# design.net
KiCad netlist of a schematic drawn in EasyEDA Pro
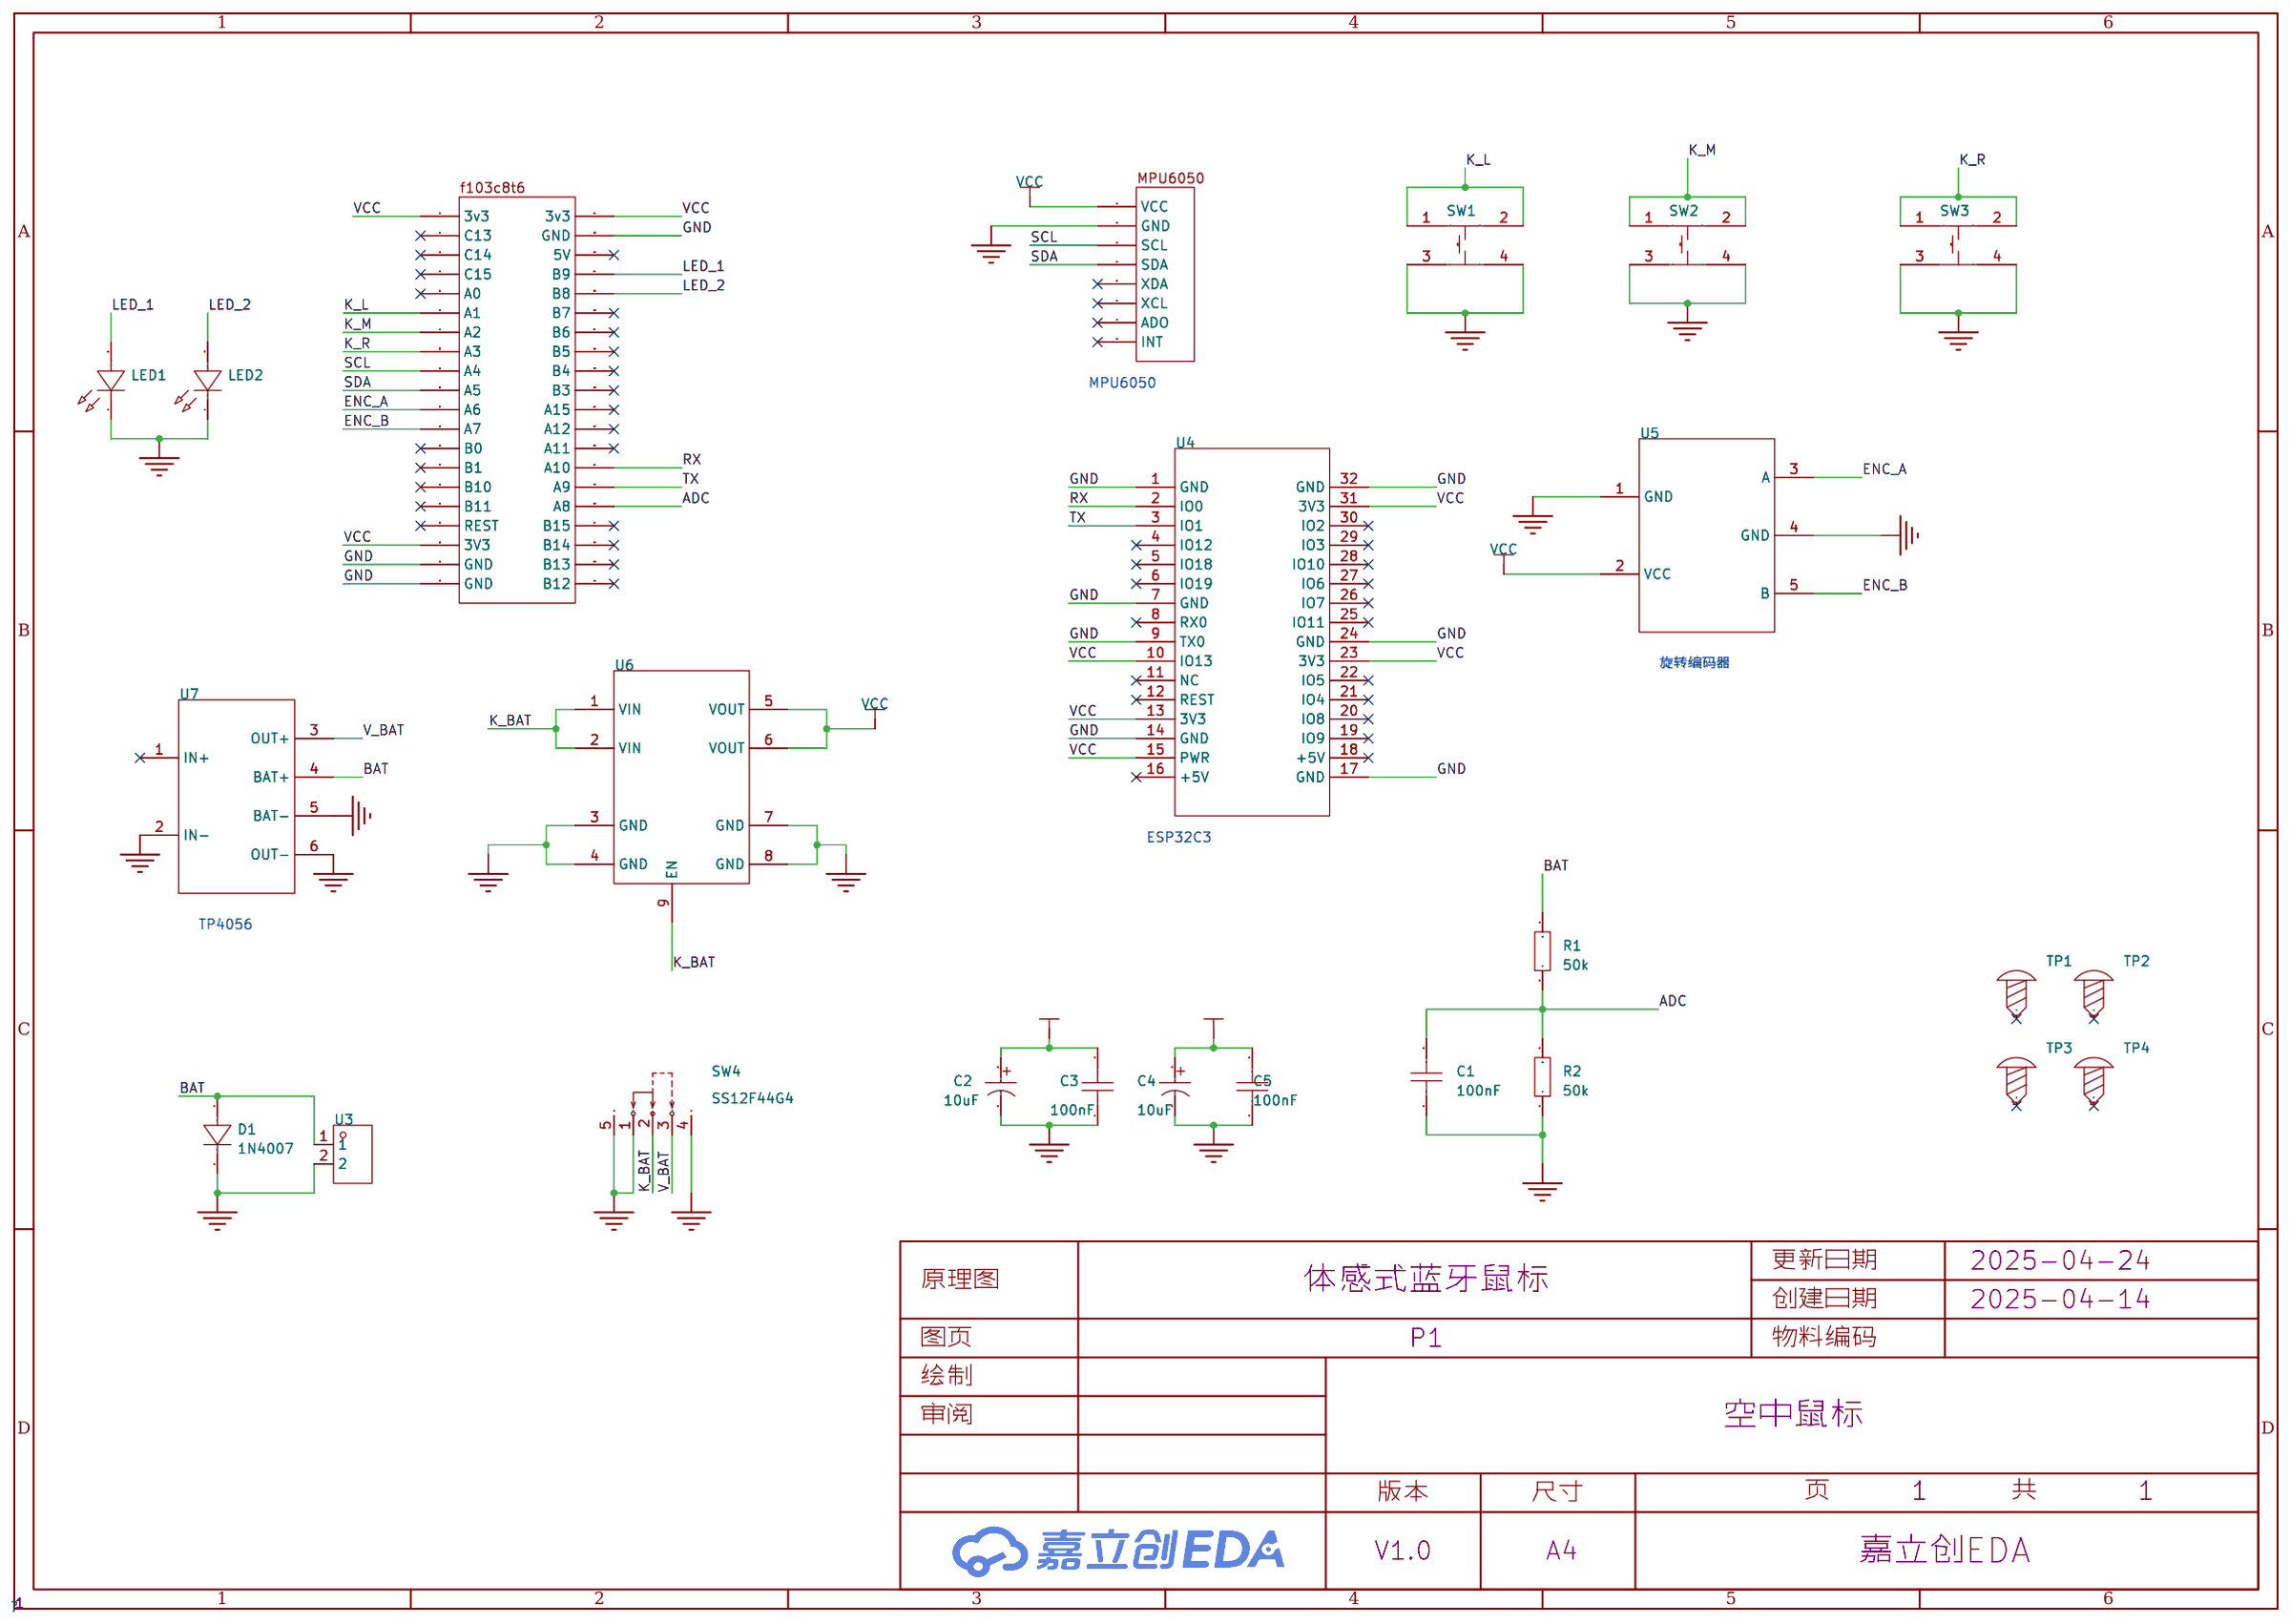
[diagram p0: schematic sheet]

(export (version "E")
  (design (tool "Eeschema 10.0.6"))
  (components
    (comp (ref "C1")
      (value "100nF")
      (footprint "easyedapro:C0603")
      (libsource (lib "easyedapro") (part "CapAcitance"))
    )
    (comp (ref "C2")
      (value "10uF")
      (footprint "easyedapro:CAP-SMD_BD4.0-L4.3-W4.3-FD")
      (description "容值:10uF;精度:±20%;额定电压:35V;纹波电流:15mA@120Hz;等效串联电阻(ESR):-;")
      (fields (field (name "Manufacturer Part") "RVT1V100M0405") (field (name "Manufacturer") "ROQANG(容强)"))
      (libsource (lib "easyedapro") (part "RVT1V100M0405-C72485"))
    )
    (comp (ref "C3")
      (value "100nF")
      (footprint "easyedapro:C0603")
      (description "容值:100nF;精度:±10%;额定电压:50V;材质(温度系数):X7R;")
      (fields
        (field (name "Manufacturer Part") "CC0603KRX7R9BB104")
        (field (name "Manufacturer") "YAGEO(国巨)")
      )
      (libsource (lib "easyedapro") (part "CC0603KRX7R9BB104"))
    )
    (comp (ref "C4")
      (value "10uF")
      (footprint "easyedapro:CAP-SMD_BD4.0-L4.3-W4.3-FD")
      (description "容值:10uF;精度:±20%;额定电压:35V;纹波电流:15mA@120Hz;等效串联电阻(ESR):-;")
      (fields (field (name "Manufacturer Part") "RVT1V100M0405") (field (name "Manufacturer") "ROQANG(容强)"))
      (libsource (lib "easyedapro") (part "RVT1V100M0405-C72485"))
    )
    (comp (ref "C5")
      (value "100nF")
      (footprint "easyedapro:C0603")
      (description "容值:100nF;精度:±10%;额定电压:50V;材质(温度系数):X7R;")
      (fields
        (field (name "Manufacturer Part") "CC0603KRX7R9BB104")
        (field (name "Manufacturer") "YAGEO(国巨)")
      )
      (libsource (lib "easyedapro") (part "CC0603KRX7R9BB104"))
    )
    (comp (ref "D1")
      (value "1N4007")
      (footprint "easyedapro:SMA_L4.3-W2.5-LS5.0-RD")
      (description "二极管配置:独立式;正向压降(Vf):1.1V@1A;直流反向耐压(Vr):1kV;整流电流:1A;")
      (fields (field (name "Manufacturer") "TWGMC(台湾迪嘉)"))
      (libsource (lib "easyedapro") (part "1N4007_C727081"))
    )
    (comp (ref "LED1")
      (value "521-9210F")
      (footprint "easyedapro:LED-TH_BD3.0-P2.54-RD")
      (fields (field (name "Manufacturer") "Dialight"))
      (libsource (lib "easyedapro") (part "521-9210F"))
    )
    (comp (ref "LED2")
      (value "521-9210F")
      (footprint "easyedapro:LED-TH_BD3.0-P2.54-RD")
      (fields (field (name "Manufacturer") "Dialight"))
      (libsource (lib "easyedapro") (part "521-9210F"))
    )
    (comp (ref "R1") (value "50k") (footprint "easyedapro:R0603") (libsource (lib "easyedapro") (part "电阻")))
    (comp (ref "R2") (value "50k") (footprint "easyedapro:R0603") (libsource (lib "easyedapro") (part "电阻")))
    (comp (ref "SCREW1")
      (value "TP1")
      (footprint "easyedapro:M3螺丝")
      (libsource (lib "easyedapro") (part "螺丝孔"))
    )
    (comp (ref "SCREW2")
      (value "TP2")
      (footprint "easyedapro:M3螺丝")
      (libsource (lib "easyedapro") (part "螺丝孔"))
    )
    (comp (ref "SCREW3")
      (value "TP3")
      (footprint "easyedapro:M3螺丝")
      (libsource (lib "easyedapro") (part "螺丝孔"))
    )
    (comp (ref "SCREW4")
      (value "TP4")
      (footprint "easyedapro:M3螺丝")
      (libsource (lib "easyedapro") (part "螺丝孔"))
    )
    (comp (ref "SW1")
      (value "TS-1002-07026")
      (footprint "easyedapro:SW-TH_4P-L6.0-W6.0-P4.50-LS6.5")
      (description "电路结构:单刀单掷;按钮形状:圆形按钮;安装方式:直插;开关长度:6mm;开关宽度:6mm;开关高度:7mm;触点电流:50mA;额定电压(DC):12V;带灯:-;机械寿命:-;")
      (fields (field (name "Manufacturer") "XUNPU(讯普)"))
      (libsource (lib "easyedapro") (part "TS-1002-07026"))
    )
    (comp (ref "SW2")
      (value "TS-1002-07026")
      (footprint "easyedapro:SW-TH_4P-L6.0-W6.0-P4.50-LS6.5")
      (description "电路结构:单刀单掷;按钮形状:圆形按钮;安装方式:直插;开关长度:6mm;开关宽度:6mm;开关高度:7mm;触点电流:50mA;额定电压(DC):12V;带灯:-;机械寿命:-;")
      (fields (field (name "Manufacturer") "XUNPU(讯普)"))
      (libsource (lib "easyedapro") (part "TS-1002-07026"))
    )
    (comp (ref "SW3")
      (value "TS-1002-07026")
      (footprint "easyedapro:SW-TH_4P-L6.0-W6.0-P4.50-LS6.5")
      (description "电路结构:单刀单掷;按钮形状:圆形按钮;安装方式:直插;开关长度:6mm;开关宽度:6mm;开关高度:7mm;触点电流:50mA;额定电压(DC):12V;带灯:-;机械寿命:-;")
      (fields (field (name "Manufacturer") "XUNPU(讯普)"))
      (libsource (lib "easyedapro") (part "TS-1002-07026"))
    )
    (comp (ref "SW4")
      (value "SS12F44G4")
      (footprint "easyedapro:SW-TH_SHOU-HAN_SS12F44G4")
      (description "电路结构:单刀双掷;安装方式:直插;开关颜色:-;额定电流(DC):300mA;额定电压(DC):50V;额定电流(AC):-;额定电压(AC):-;机械寿命:5千次;")
      (fields (field (name "Manufacturer") "SHOU HAN(首韩)"))
      (libsource (lib "easyedapro") (part "SS12F44G4"))
    )
    (comp (ref "U1")
      (value "~")
      (footprint "easyedapro:stm32f103c8t6最小系统板")
      (libsource (lib "easyedapro") (part "stm32f103c8t6最小系统板"))
    )
    (comp (ref "U2")
      (value "~")
      (footprint "easyedapro:MPU6050")
      (libsource (lib "easyedapro") (part "MPU6050"))
    )
    (comp (ref "U3")
      (value "XY-XHB2.54-2A21")
      (footprint "easyedapro:HDR-TH_2P-P2.50-H-F-W7.3-N")
      (description "插针结构:1x2P;间距:2.54mm;安装方式:弯插;总PIN数:2P;排数:1;每排PIN数:2;行距:2.54mm;额定电流:2A;工作温度范围:-25°C~+85°C;")
      (fields (field (name "Manufacturer") "XYECONN(辛译)"))
      (libsource (lib "easyedapro") (part "XY-XHB2.54-2A21"))
    )
    (comp (ref "U4")
      (value "~")
      (footprint "easyedapro:ESP32C3核心板")
      (libsource (lib "easyedapro") (part "ESP32C3核心板"))
    )
    (comp (ref "U5") (value "~") (footprint "easyedapro:旋转编码器") (libsource (lib "easyedapro") (part "旋转编码器")))
    (comp (ref "U6")
      (value "~")
      (footprint "easyedapro:TPS63000")
      (libsource (lib "easyedapro") (part "TPS63000"))
    )
    (comp (ref "U7")
      (value "~")
      (footprint "easyedapro:TP4056")
      (libsource (lib "easyedapro") (part "TP4056模块"))
    )
  )
  (nets
    (net (code "1") (name "/ADC") (class "Default")
      (node (ref "C1") (pin "2") (pinfunction "2_2") (pintype "input"))
      (node (ref "R1") (pin "1") (pinfunction "1_1") (pintype "input"))
      (node (ref "R2") (pin "2") (pinfunction "2_2") (pintype "input"))
      (node (ref "U1") (pin "36") (pinfunction "A8_36") (pintype "input"))
    )
    (net (code "2") (name "/BAT") (class "Default")
      (node (ref "D1") (pin "2") (pinfunction "A_2") (pintype "unspecified"))
      (node (ref "R1") (pin "2") (pinfunction "2_2") (pintype "input"))
      (node (ref "U3") (pin "1") (pinfunction "1_1") (pintype "unspecified"))
      (node (ref "U7") (pin "4") (pinfunction "BAT+_4") (pintype "input"))
    )
    (net (code "3") (name "/ENC_A") (class "Default")
      (node (ref "U1") (pin "11") (pinfunction "A6_11") (pintype "input"))
      (node (ref "U5") (pin "3") (pinfunction "A_3") (pintype "input"))
    )
    (net (code "4") (name "/ENC_B") (class "Default")
      (node (ref "U1") (pin "12") (pinfunction "A7_12") (pintype "input"))
      (node (ref "U5") (pin "5") (pinfunction "B_5") (pintype "input"))
    )
    (net (code "5") (name "/K_L") (class "Default")
      (node (ref "SW1") (pin "1") (pinfunction "1_1") (pintype "unspecified"))
      (node (ref "SW1") (pin "2") (pinfunction "2_2") (pintype "unspecified"))
      (node (ref "U1") (pin "6") (pinfunction "A1_6") (pintype "input"))
    )
    (net (code "6") (name "/K_M") (class "Default")
      (node (ref "SW2") (pin "1") (pinfunction "1_1") (pintype "unspecified"))
      (node (ref "SW2") (pin "2") (pinfunction "2_2") (pintype "unspecified"))
      (node (ref "U1") (pin "7") (pinfunction "A2_7") (pintype "input"))
    )
    (net (code "7") (name "/K_R") (class "Default")
      (node (ref "SW3") (pin "1") (pinfunction "1_1") (pintype "unspecified"))
      (node (ref "SW3") (pin "2") (pinfunction "2_2") (pintype "unspecified"))
      (node (ref "U1") (pin "8") (pinfunction "A3_8") (pintype "input"))
    )
    (net (code "8") (name "/LED_1") (class "Default")
      (node (ref "LED1") (pin "2") (pinfunction "A_2") (pintype "unspecified"))
      (node (ref "U1") (pin "24") (pinfunction "B9_24") (pintype "input"))
    )
    (net (code "9") (name "/LED_2") (class "Default")
      (node (ref "LED2") (pin "2") (pinfunction "A_2") (pintype "unspecified"))
      (node (ref "U1") (pin "25") (pinfunction "B8_25") (pintype "input"))
    )
    (net (code "10") (name "/RX") (class "Default")
      (node (ref "U1") (pin "34") (pinfunction "A10_34") (pintype "input"))
      (node (ref "U4") (pin "2") (pinfunction "IO0_2") (pintype "input"))
    )
    (net (code "11") (name "/SCL") (class "Default")
      (node (ref "U1") (pin "9") (pinfunction "A4_9") (pintype "input"))
      (node (ref "U2") (pin "3") (pinfunction "SCL_3") (pintype "input"))
    )
    (net (code "12") (name "/SDA") (class "Default")
      (node (ref "U1") (pin "10") (pinfunction "A5_10") (pintype "input"))
      (node (ref "U2") (pin "4") (pinfunction "SDA_4") (pintype "input"))
    )
    (net (code "13") (name "/TX") (class "Default")
      (node (ref "U1") (pin "35") (pinfunction "A9_35") (pintype "input"))
      (node (ref "U4") (pin "3") (pinfunction "IO1_3") (pintype "input"))
    )
    (net (code "14") (name "/V_BAT") (class "Default")
      (node (ref "SW4") (pin "3") (pinfunction "3_3") (pintype "unspecified"))
      (node (ref "U7") (pin "3") (pinfunction "OUT+_3") (pintype "input"))
    )
    (net (code "15") (name "GND") (class "Default")
      (node (ref "C1") (pin "1") (pinfunction "1_1") (pintype "input"))
      (node (ref "C2") (pin "2") (pinfunction "2_2") (pintype "input"))
      (node (ref "C3") (pin "1") (pinfunction "1_1") (pintype "unspecified"))
      (node (ref "C4") (pin "2") (pinfunction "2_2") (pintype "input"))
      (node (ref "C5") (pin "1") (pinfunction "1_1") (pintype "unspecified"))
      (node (ref "D1") (pin "1") (pinfunction "K_1") (pintype "unspecified"))
      (node (ref "LED1") (pin "1") (pinfunction "K_1") (pintype "unspecified"))
      (node (ref "LED2") (pin "1") (pinfunction "K_1") (pintype "unspecified"))
      (node (ref "R2") (pin "1") (pinfunction "1_1") (pintype "input"))
      (node (ref "SW1") (pin "3") (pinfunction "3_3") (pintype "unspecified"))
      (node (ref "SW1") (pin "4") (pinfunction "4_4") (pintype "unspecified"))
      (node (ref "SW2") (pin "3") (pinfunction "3_3") (pintype "unspecified"))
      (node (ref "SW2") (pin "4") (pinfunction "4_4") (pintype "unspecified"))
      (node (ref "SW3") (pin "3") (pinfunction "3_3") (pintype "unspecified"))
      (node (ref "SW3") (pin "4") (pinfunction "4_4") (pintype "unspecified"))
      (node (ref "SW4") (pin "1") (pinfunction "1_1") (pintype "unspecified"))
      (node (ref "SW4") (pin "4") (pinfunction "4_4") (pintype "unspecified"))
      (node (ref "SW4") (pin "5") (pinfunction "5_5") (pintype "unspecified"))
      (node (ref "U1") (pin "19") (pinfunction "GND_19") (pintype "input"))
      (node (ref "U1") (pin "20") (pinfunction "GND_20") (pintype "input"))
      (node (ref "U1") (pin "22") (pinfunction "GND_22") (pintype "input"))
      (node (ref "U2") (pin "2") (pinfunction "GND_2") (pintype "input"))
      (node (ref "U3") (pin "2") (pinfunction "2_2") (pintype "unspecified"))
      (node (ref "U4") (pin "1") (pinfunction "GND_1") (pintype "input"))
      (node (ref "U4") (pin "14") (pinfunction "GND_14") (pintype "input"))
      (node (ref "U4") (pin "17") (pinfunction "GND_17") (pintype "input"))
      (node (ref "U4") (pin "24") (pinfunction "GND_24") (pintype "input"))
      (node (ref "U4") (pin "32") (pinfunction "GND_32") (pintype "input"))
      (node (ref "U4") (pin "7") (pinfunction "GND_7") (pintype "input"))
      (node (ref "U4") (pin "9") (pinfunction "TX0_9") (pintype "input"))
      (node (ref "U5") (pin "1") (pinfunction "GND_1") (pintype "input"))
      (node (ref "U5") (pin "4") (pinfunction "GND_4") (pintype "input"))
      (node (ref "U6") (pin "3") (pinfunction "GND_3") (pintype "input"))
      (node (ref "U6") (pin "4") (pinfunction "GND_4") (pintype "input"))
      (node (ref "U6") (pin "7") (pinfunction "GND_7") (pintype "input"))
      (node (ref "U6") (pin "8") (pinfunction "GND_8") (pintype "input"))
      (node (ref "U7") (pin "2") (pinfunction "IN-_2") (pintype "input"))
      (node (ref "U7") (pin "5") (pinfunction "BAT-_5") (pintype "input"))
      (node (ref "U7") (pin "6") (pinfunction "OUT-_6") (pintype "input"))
    )
    (net (code "16") (name "K_BAT") (class "Default")
      (node (ref "C2") (pin "1") (pinfunction "1_1") (pintype "input"))
      (node (ref "C3") (pin "2") (pinfunction "2_2") (pintype "unspecified"))
      (node (ref "SW4") (pin "2") (pinfunction "2_2") (pintype "unspecified"))
      (node (ref "U6") (pin "1") (pinfunction "VIN_1") (pintype "input"))
      (node (ref "U6") (pin "2") (pinfunction "VIN_2") (pintype "input"))
      (node (ref "U6") (pin "9") (pinfunction "EN_9") (pintype "input"))
    )
    (net (code "17") (name "VCC") (class "Default")
      (node (ref "C4") (pin "1") (pinfunction "1_1") (pintype "input"))
      (node (ref "C5") (pin "2") (pinfunction "2_2") (pintype "unspecified"))
      (node (ref "U1") (pin "1") (pinfunction "3v3_1") (pintype "input"))
      (node (ref "U1") (pin "18") (pinfunction "3V3_18") (pintype "input"))
      (node (ref "U1") (pin "21") (pinfunction "3v3_21") (pintype "input"))
      (node (ref "U2") (pin "1") (pinfunction "VCC_1") (pintype "input"))
      (node (ref "U4") (pin "10") (pinfunction "IO13_10") (pintype "input"))
      (node (ref "U4") (pin "13") (pinfunction "3V3_13") (pintype "input"))
      (node (ref "U4") (pin "15") (pinfunction "PWR_15") (pintype "input"))
      (node (ref "U4") (pin "23") (pinfunction "3V3_23") (pintype "input"))
      (node (ref "U4") (pin "31") (pinfunction "3V3_31") (pintype "input"))
      (node (ref "U5") (pin "2") (pinfunction "VCC_2") (pintype "input"))
      (node (ref "U6") (pin "5") (pinfunction "VOUT_5") (pintype "input"))
      (node (ref "U6") (pin "6") (pinfunction "VOUT_6") (pintype "input"))
    )
    (net (code "18") (name "unconnected-(SCREW1-Pad1)") (class "Default")
      (node (ref "SCREW1") (pin "1") (pinfunction "1_1") (pintype "input+no_connect"))
    )
    (net (code "19") (name "unconnected-(SCREW2-Pad1)") (class "Default")
      (node (ref "SCREW2") (pin "1") (pinfunction "1_1") (pintype "input+no_connect"))
    )
    (net (code "20") (name "unconnected-(SCREW3-Pad1)") (class "Default")
      (node (ref "SCREW3") (pin "1") (pinfunction "1_1") (pintype "input+no_connect"))
    )
    (net (code "21") (name "unconnected-(SCREW4-Pad1)") (class "Default")
      (node (ref "SCREW4") (pin "1") (pinfunction "1_1") (pintype "input+no_connect"))
    )
    (net (code "22") (name "unconnected-(U1-5V-Pad23)") (class "Default")
      (node (ref "U1") (pin "23") (pinfunction "5V_23") (pintype "input+no_connect"))
    )
    (net (code "23") (name "unconnected-(U1-A0-Pad5)") (class "Default")
      (node (ref "U1") (pin "5") (pinfunction "A0_5") (pintype "input+no_connect"))
    )
    (net (code "24") (name "unconnected-(U1-A11-Pad33)") (class "Default")
      (node (ref "U1") (pin "33") (pinfunction "A11_33") (pintype "input+no_connect"))
    )
    (net (code "25") (name "unconnected-(U1-A12-Pad32)") (class "Default")
      (node (ref "U1") (pin "32") (pinfunction "A12_32") (pintype "input+no_connect"))
    )
    (net (code "26") (name "unconnected-(U1-A15-Pad31)") (class "Default")
      (node (ref "U1") (pin "31") (pinfunction "A15_31") (pintype "input+no_connect"))
    )
    (net (code "27") (name "unconnected-(U1-B0-Pad13)") (class "Default")
      (node (ref "U1") (pin "13") (pinfunction "B0_13") (pintype "input+no_connect"))
    )
    (net (code "28") (name "unconnected-(U1-B1-Pad14)") (class "Default")
      (node (ref "U1") (pin "14") (pinfunction "B1_14") (pintype "input+no_connect"))
    )
    (net (code "29") (name "unconnected-(U1-B3-Pad30)") (class "Default")
      (node (ref "U1") (pin "30") (pinfunction "B3_30") (pintype "input+no_connect"))
    )
    (net (code "30") (name "unconnected-(U1-B4-Pad29)") (class "Default")
      (node (ref "U1") (pin "29") (pinfunction "B4_29") (pintype "input+no_connect"))
    )
    (net (code "31") (name "unconnected-(U1-B5-Pad28)") (class "Default")
      (node (ref "U1") (pin "28") (pinfunction "B5_28") (pintype "input+no_connect"))
    )
    (net (code "32") (name "unconnected-(U1-B6-Pad27)") (class "Default")
      (node (ref "U1") (pin "27") (pinfunction "B6_27") (pintype "input+no_connect"))
    )
    (net (code "33") (name "unconnected-(U1-B7-Pad26)") (class "Default")
      (node (ref "U1") (pin "26") (pinfunction "B7_26") (pintype "input+no_connect"))
    )
    (net (code "34") (name "unconnected-(U1-B10-Pad15)") (class "Default")
      (node (ref "U1") (pin "15") (pinfunction "B10_15") (pintype "input+no_connect"))
    )
    (net (code "35") (name "unconnected-(U1-B11-Pad16)") (class "Default")
      (node (ref "U1") (pin "16") (pinfunction "B11_16") (pintype "input+no_connect"))
    )
    (net (code "36") (name "unconnected-(U1-B12-Pad40)") (class "Default")
      (node (ref "U1") (pin "40") (pinfunction "B12_40") (pintype "input+no_connect"))
    )
    (net (code "37") (name "unconnected-(U1-B13-Pad39)") (class "Default")
      (node (ref "U1") (pin "39") (pinfunction "B13_39") (pintype "input+no_connect"))
    )
    (net (code "38") (name "unconnected-(U1-B14-Pad38)") (class "Default")
      (node (ref "U1") (pin "38") (pinfunction "B14_38") (pintype "input+no_connect"))
    )
    (net (code "39") (name "unconnected-(U1-B15-Pad37)") (class "Default")
      (node (ref "U1") (pin "37") (pinfunction "B15_37") (pintype "input+no_connect"))
    )
    (net (code "40") (name "unconnected-(U1-C13-Pad2)") (class "Default")
      (node (ref "U1") (pin "2") (pinfunction "C13_2") (pintype "input+no_connect"))
    )
    (net (code "41") (name "unconnected-(U1-C14-Pad3)") (class "Default")
      (node (ref "U1") (pin "3") (pinfunction "C14_3") (pintype "input+no_connect"))
    )
    (net (code "42") (name "unconnected-(U1-C15-Pad4)") (class "Default")
      (node (ref "U1") (pin "4") (pinfunction "C15_4") (pintype "input+no_connect"))
    )
    (net (code "43") (name "unconnected-(U1-REST-Pad17)") (class "Default")
      (node (ref "U1") (pin "17") (pinfunction "REST_17") (pintype "input+no_connect"))
    )
    (net (code "44") (name "unconnected-(U2-ADO-Pad7)") (class "Default")
      (node (ref "U2") (pin "7") (pinfunction "ADO_7") (pintype "input+no_connect"))
    )
    (net (code "45") (name "unconnected-(U2-INT-Pad8)") (class "Default")
      (node (ref "U2") (pin "8") (pinfunction "INT_8") (pintype "input+no_connect"))
    )
    (net (code "46") (name "unconnected-(U2-XCL-Pad6)") (class "Default")
      (node (ref "U2") (pin "6") (pinfunction "XCL_6") (pintype "input+no_connect"))
    )
    (net (code "47") (name "unconnected-(U2-XDA-Pad5)") (class "Default")
      (node (ref "U2") (pin "5") (pinfunction "XDA_5") (pintype "input+no_connect"))
    )
    (net (code "48") (name "unconnected-(U4-+5V-Pad16)") (class "Default")
      (node (ref "U4") (pin "16") (pinfunction "+5V_16") (pintype "input+no_connect"))
    )
    (net (code "49") (name "unconnected-(U4-+5V-Pad18)") (class "Default")
      (node (ref "U4") (pin "18") (pinfunction "+5V_18") (pintype "input+no_connect"))
    )
    (net (code "50") (name "unconnected-(U4-IO2-Pad30)") (class "Default")
      (node (ref "U4") (pin "30") (pinfunction "IO2_30") (pintype "input+no_connect"))
    )
    (net (code "51") (name "unconnected-(U4-IO3-Pad29)") (class "Default")
      (node (ref "U4") (pin "29") (pinfunction "IO3_29") (pintype "input+no_connect"))
    )
    (net (code "52") (name "unconnected-(U4-IO4-Pad21)") (class "Default")
      (node (ref "U4") (pin "21") (pinfunction "IO4_21") (pintype "input+no_connect"))
    )
    (net (code "53") (name "unconnected-(U4-IO5-Pad22)") (class "Default")
      (node (ref "U4") (pin "22") (pinfunction "IO5_22") (pintype "input+no_connect"))
    )
    (net (code "54") (name "unconnected-(U4-IO6-Pad27)") (class "Default")
      (node (ref "U4") (pin "27") (pinfunction "IO6_27") (pintype "input+no_connect"))
    )
    (net (code "55") (name "unconnected-(U4-IO7-Pad26)") (class "Default")
      (node (ref "U4") (pin "26") (pinfunction "IO7_26") (pintype "input+no_connect"))
    )
    (net (code "56") (name "unconnected-(U4-IO8-Pad20)") (class "Default")
      (node (ref "U4") (pin "20") (pinfunction "IO8_20") (pintype "input+no_connect"))
    )
    (net (code "57") (name "unconnected-(U4-IO9-Pad19)") (class "Default")
      (node (ref "U4") (pin "19") (pinfunction "IO9_19") (pintype "input+no_connect"))
    )
    (net (code "58") (name "unconnected-(U4-IO10-Pad28)") (class "Default")
      (node (ref "U4") (pin "28") (pinfunction "IO10_28") (pintype "input+no_connect"))
    )
    (net (code "59") (name "unconnected-(U4-IO11-Pad25)") (class "Default")
      (node (ref "U4") (pin "25") (pinfunction "IO11_25") (pintype "input+no_connect"))
    )
    (net (code "60") (name "unconnected-(U4-IO12-Pad4)") (class "Default")
      (node (ref "U4") (pin "4") (pinfunction "IO12_4") (pintype "input+no_connect"))
    )
    (net (code "61") (name "unconnected-(U4-IO18-Pad5)") (class "Default")
      (node (ref "U4") (pin "5") (pinfunction "IO18_5") (pintype "input+no_connect"))
    )
    (net (code "62") (name "unconnected-(U4-IO19-Pad6)") (class "Default")
      (node (ref "U4") (pin "6") (pinfunction "IO19_6") (pintype "input+no_connect"))
    )
    (net (code "63") (name "unconnected-(U4-NC-Pad11)") (class "Default")
      (node (ref "U4") (pin "11") (pinfunction "NC_11") (pintype "input+no_connect"))
    )
    (net (code "64") (name "unconnected-(U4-REST-Pad12)") (class "Default")
      (node (ref "U4") (pin "12") (pinfunction "REST_12") (pintype "input+no_connect"))
    )
    (net (code "65") (name "unconnected-(U4-RX0-Pad8)") (class "Default")
      (node (ref "U4") (pin "8") (pinfunction "RX0_8") (pintype "input+no_connect"))
    )
    (net (code "66") (name "unconnected-(U7-IN+-Pad1)") (class "Default")
      (node (ref "U7") (pin "1") (pinfunction "IN+_1") (pintype "input+no_connect"))
    )
  )
)
